# SENSOR.net
KiCad netlist of a schematic drawn in Altium Designer
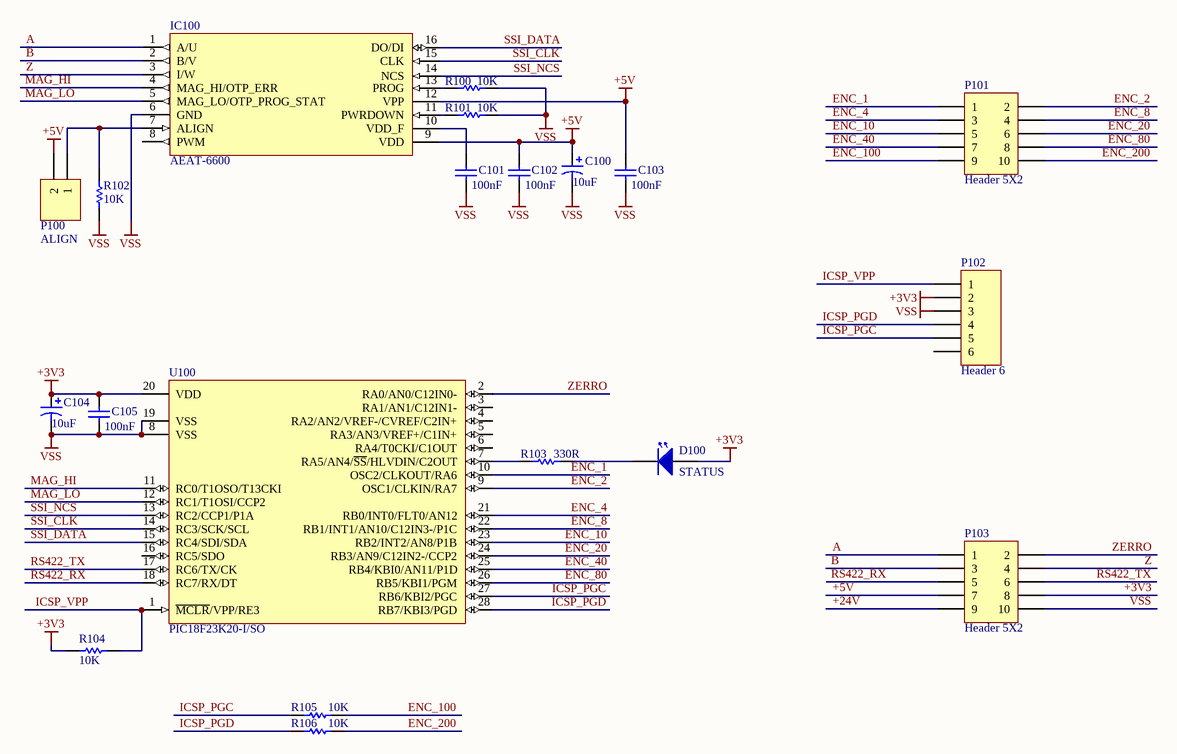
[diagram p0: SENSOR.SchDoc]

(export (version "E")
  (design (tool "Eeschema 10.0.6"))
  (components
    (comp (ref "C100")
      (value "10uF")
      (footprint "C")
      (description "Solid Aluminum Capacitor with Organic Semiconductor Electrolyte: 10uF, 16V, Bulk Pack")
      (fields (field (name "PUBLISHER") "Altium Limited"))
      (libsource (lib "Vishay Electrolytic Radial-Lead Capacitor") (part "94SC106X0016CBP"))
    )
    (comp (ref "C101")
      (value "100nF")
      (footprint "0805")
      (description "Ceramic Chip Capacitor - Standard")
      (fields (field (name "PUBLISHER") "Altium Limited"))
      (libsource (lib "KEMET Chip Capacitor") (part "C0805"))
    )
    (comp (ref "C102")
      (value "100nF")
      (footprint "0805")
      (description "Ceramic Chip Capacitor - Standard")
      (fields (field (name "PUBLISHER") "Altium Limited"))
      (libsource (lib "KEMET Chip Capacitor") (part "C0805"))
    )
    (comp (ref "C103")
      (value "100nF")
      (footprint "0805")
      (description "Ceramic Chip Capacitor - Standard")
      (fields (field (name "PUBLISHER") "Altium Limited"))
      (libsource (lib "KEMET Chip Capacitor") (part "C0805"))
    )
    (comp (ref "C104")
      (value "10uF")
      (footprint "C")
      (description "Solid Aluminum Capacitor with Organic Semiconductor Electrolyte: 10uF, 16V, Bulk Pack")
      (fields (field (name "PUBLISHER") "Altium Limited"))
      (libsource (lib "Vishay Electrolytic Radial-Lead Capacitor") (part "94SC106X0016CBP"))
    )
    (comp (ref "C105")
      (value "100nF")
      (footprint "0805")
      (description "Ceramic Chip Capacitor - Standard")
      (fields (field (name "PUBLISHER") "Altium Limited"))
      (libsource (lib "KEMET Chip Capacitor") (part "C0805"))
    )
    (comp (ref "D100")
      (value "STATUS")
      (footprint "LED 3mm")
      (description "LED dioda 3 mm")
      (libsource (lib "Schlib1") (part "LED 3mm yellow"))
    )
    (comp (ref "IC100")
      (value "AEAT-6600")
      (footprint "TSSOP16")
      (description "Absolute encoder IC")
      (libsource (lib "ABS_ENC") (part "AEAT-6600"))
    )
    (comp (ref "P100")
      (value "ALIGN")
      (footprint "HDR1X2")
      (description "Header, 2-Pin")
      (fields (field (name "PUBLISHER") "Altium Limited"))
      (libsource (lib "Miscellaneous Connectors") (part "Header 2"))
    )
    (comp (ref "P101")
      (value "Header 5X2")
      (footprint "HDR2X5")
      (description "Header, 5-Pin, Dual row")
      (fields (field (name "PUBLISHER") "Altium Limited"))
      (libsource (lib "Miscellaneous Connectors") (part "Header 5X2"))
    )
    (comp (ref "P102")
      (value "Header 6")
      (footprint "HDR1X6")
      (description "Header, 6-Pin")
      (fields (field (name "PUBLISHER") "Altium Limited"))
      (libsource (lib "Miscellaneous Connectors") (part "Header 6"))
    )
    (comp (ref "P103")
      (value "Header 5X2")
      (footprint "HDR2X5")
      (description "Header, 5-Pin, Dual row")
      (fields (field (name "PUBLISHER") "Altium Limited"))
      (libsource (lib "Miscellaneous Connectors") (part "Header 5X2"))
    )
    (comp (ref "R100")
      (value "10K")
      (footprint "ERA-0603")
      (fields (field (name "PUBLISHER") "Altium Limited"))
      (libsource (lib "Panasonic Resistor") (part "ERAV"))
    )
    (comp (ref "R101")
      (value "10K")
      (footprint "ERA-0603")
      (fields (field (name "PUBLISHER") "Altium Limited"))
      (libsource (lib "Panasonic Resistor") (part "ERAV"))
    )
    (comp (ref "R102")
      (value "10K")
      (footprint "ERA-0603")
      (fields (field (name "PUBLISHER") "Altium Limited"))
      (libsource (lib "Panasonic Resistor") (part "ERAV"))
    )
    (comp (ref "R103")
      (value "330R")
      (footprint "ERA-0603")
      (fields (field (name "PUBLISHER") "Altium Limited"))
      (libsource (lib "Panasonic Resistor") (part "ERAV"))
    )
    (comp (ref "R104")
      (value "10K")
      (footprint "ERA-0603")
      (fields (field (name "PUBLISHER") "Altium Limited"))
      (libsource (lib "Panasonic Resistor") (part "ERAV"))
    )
    (comp (ref "R105")
      (value "10K")
      (footprint "ERA-0603")
      (fields (field (name "PUBLISHER") "Altium Limited"))
      (libsource (lib "Panasonic Resistor") (part "ERAV"))
    )
    (comp (ref "R106")
      (value "10K")
      (footprint "ERA-0603")
      (fields (field (name "PUBLISHER") "Altium Limited"))
      (libsource (lib "Panasonic Resistor") (part "ERAV"))
    )
    (comp (ref "U100")
      (value "PIC18F23K20-I/SO")
      (footprint "SOIC-SO28_N")
      (description "Flash Microcontroller with nanoWatt XLP Technology, 28-pin SOIC, Industrial Temperature")
      (fields (field (name "PUBLISHER") "Altium Limited"))
      (libsource (lib "Microchip Microcontroller 8-Bit PIC18") (part "PIC18F23K20-I/SO"))
    )
  )
  (nets
    (net (code "1") (name "+3V3") (class "Default")
      (node (ref "C104") (pin "1") (pinfunction "1_1") (pintype "passive"))
      (node (ref "C105") (pin "2") (pinfunction "2_2") (pintype "passive"))
      (node (ref "D100") (pin "2") (pinfunction "2_2") (pintype "passive"))
      (node (ref "P102") (pin "2") (pinfunction "2_2") (pintype "passive"))
      (node (ref "P103") (pin "8") (pinfunction "8_8") (pintype "passive"))
      (node (ref "R104") (pin "2") (pinfunction "2_2") (pintype "passive"))
      (node (ref "U100") (pin "20") (pinfunction "VDD_20") (pintype "power_in"))
    )
    (net (code "2") (name "+5V") (class "Default")
      (node (ref "C100") (pin "1") (pinfunction "1_1") (pintype "passive"))
      (node (ref "C102") (pin "2") (pinfunction "2_2") (pintype "passive"))
      (node (ref "C103") (pin "2") (pinfunction "2_2") (pintype "passive"))
      (node (ref "IC100") (pin "12") (pinfunction "VPP_12") (pintype "power_in"))
      (node (ref "IC100") (pin "9") (pinfunction "VDD_9") (pintype "power_in"))
      (node (ref "P100") (pin "2") (pinfunction "2_2") (pintype "passive"))
      (node (ref "P103") (pin "7") (pinfunction "7_7") (pintype "passive"))
    )
    (net (code "3") (name "/+24V") (class "Default")
      (node (ref "P103") (pin "9") (pinfunction "9_9") (pintype "passive"))
    )
    (net (code "4") (name "/A") (class "Default")
      (node (ref "IC100") (pin "1") (pinfunction "A/U_1") (pintype "output"))
      (node (ref "P103") (pin "1") (pinfunction "1_1") (pintype "passive"))
    )
    (net (code "5") (name "/B") (class "Default")
      (node (ref "IC100") (pin "2") (pinfunction "B/V_2") (pintype "output"))
      (node (ref "P103") (pin "3") (pinfunction "3_3") (pintype "passive"))
    )
    (net (code "6") (name "/ENC_1") (class "Default")
      (node (ref "P101") (pin "1") (pinfunction "1_1") (pintype "passive"))
      (node (ref "U100") (pin "10") (pinfunction "OSC2/CLKOUT/RA6_10") (pintype "bidirectional"))
    )
    (net (code "7") (name "/ENC_2") (class "Default")
      (node (ref "P101") (pin "2") (pinfunction "2_2") (pintype "passive"))
      (node (ref "U100") (pin "9") (pinfunction "OSC1/CLKIN/RA7_9") (pintype "bidirectional"))
    )
    (net (code "8") (name "/ENC_4") (class "Default")
      (node (ref "P101") (pin "3") (pinfunction "3_3") (pintype "passive"))
      (node (ref "U100") (pin "21") (pinfunction "RB0/INT0/FLT0/AN12_21") (pintype "bidirectional"))
    )
    (net (code "9") (name "/ENC_8") (class "Default")
      (node (ref "P101") (pin "4") (pinfunction "4_4") (pintype "passive"))
      (node (ref "U100") (pin "22") (pinfunction "RB1/INT1/AN10/C12IN3-/P1C_22") (pintype "bidirectional"))
    )
    (net (code "10") (name "/ENC_10") (class "Default")
      (node (ref "P101") (pin "5") (pinfunction "5_5") (pintype "passive"))
      (node (ref "U100") (pin "23") (pinfunction "RB2/INT2/AN8/P1B_23") (pintype "bidirectional"))
    )
    (net (code "11") (name "/ENC_20") (class "Default")
      (node (ref "P101") (pin "6") (pinfunction "6_6") (pintype "passive"))
      (node (ref "U100") (pin "24") (pinfunction "RB3/AN9/C12IN2-/CCP2_24") (pintype "bidirectional"))
    )
    (net (code "12") (name "/ENC_40") (class "Default")
      (node (ref "P101") (pin "7") (pinfunction "7_7") (pintype "passive"))
      (node (ref "U100") (pin "25") (pinfunction "RB4/KBI0/AN11/P1D_25") (pintype "bidirectional"))
    )
    (net (code "13") (name "/ENC_80") (class "Default")
      (node (ref "P101") (pin "8") (pinfunction "8_8") (pintype "passive"))
      (node (ref "U100") (pin "26") (pinfunction "RB5/KBI1/PGM_26") (pintype "bidirectional"))
    )
    (net (code "14") (name "/ENC_100") (class "Default")
      (node (ref "P101") (pin "9") (pinfunction "9_9") (pintype "passive"))
      (node (ref "R105") (pin "1") (pinfunction "1_1") (pintype "passive"))
    )
    (net (code "15") (name "/ENC_200") (class "Default")
      (node (ref "P101") (pin "10") (pinfunction "10_10") (pintype "passive"))
      (node (ref "R106") (pin "1") (pinfunction "1_1") (pintype "passive"))
    )
    (net (code "16") (name "/ICSP_PGC") (class "Default")
      (node (ref "P102") (pin "5") (pinfunction "5_5") (pintype "passive"))
      (node (ref "R105") (pin "2") (pinfunction "2_2") (pintype "passive"))
      (node (ref "U100") (pin "27") (pinfunction "RB6/KBI2/PGC_27") (pintype "bidirectional"))
    )
    (net (code "17") (name "/ICSP_PGD") (class "Default")
      (node (ref "P102") (pin "4") (pinfunction "4_4") (pintype "passive"))
      (node (ref "R106") (pin "2") (pinfunction "2_2") (pintype "passive"))
      (node (ref "U100") (pin "28") (pinfunction "RB7/KBI3/PGD_28") (pintype "bidirectional"))
    )
    (net (code "18") (name "/ICSP_VPP") (class "Default")
      (node (ref "P102") (pin "1") (pinfunction "1_1") (pintype "passive"))
      (node (ref "R104") (pin "1") (pinfunction "1_1") (pintype "passive"))
      (node (ref "U100") (pin "1") (pinfunction "~{MCLR}/VPP/RE3_1") (pintype "input"))
    )
    (net (code "19") (name "/MAG_HI") (class "Default")
      (node (ref "IC100") (pin "4") (pinfunction "MAG_HI/OTP_ERR_4") (pintype "output"))
      (node (ref "U100") (pin "11") (pinfunction "RC0/T1OSO/T13CKI_11") (pintype "bidirectional"))
    )
    (net (code "20") (name "/MAG_LO") (class "Default")
      (node (ref "IC100") (pin "5") (pinfunction "MAG_LO/OTP_PROG_STAT_5") (pintype "output"))
      (node (ref "U100") (pin "12") (pinfunction "RC1/T1OSI/CCP2_12") (pintype "bidirectional"))
    )
    (net (code "21") (name "/RS422_RX") (class "Default")
      (node (ref "P103") (pin "5") (pinfunction "5_5") (pintype "passive"))
      (node (ref "U100") (pin "18") (pinfunction "RC7/RX/DT_18") (pintype "bidirectional"))
    )
    (net (code "22") (name "/RS422_TX") (class "Default")
      (node (ref "P103") (pin "6") (pinfunction "6_6") (pintype "passive"))
      (node (ref "U100") (pin "17") (pinfunction "RC6/TX/CK_17") (pintype "bidirectional"))
    )
    (net (code "23") (name "/SSI_CLK") (class "Default")
      (node (ref "IC100") (pin "15") (pinfunction "CLK_15") (pintype "input"))
      (node (ref "U100") (pin "14") (pinfunction "RC3/SCK/SCL_14") (pintype "bidirectional"))
    )
    (net (code "24") (name "/SSI_DATA") (class "Default")
      (node (ref "IC100") (pin "16") (pinfunction "DO/DI_16") (pintype "bidirectional"))
      (node (ref "U100") (pin "15") (pinfunction "RC4/SDI/SDA_15") (pintype "bidirectional"))
    )
    (net (code "25") (name "/SSI_NCS") (class "Default")
      (node (ref "IC100") (pin "14") (pinfunction "NCS_14") (pintype "input"))
      (node (ref "U100") (pin "13") (pinfunction "RC2/CCP1/P1A_13") (pintype "bidirectional"))
    )
    (net (code "26") (name "/Z") (class "Default")
      (node (ref "IC100") (pin "3") (pinfunction "I/W_3") (pintype "output"))
      (node (ref "P103") (pin "4") (pinfunction "4_4") (pintype "passive"))
    )
    (net (code "27") (name "/ZERRO") (class "Default")
      (node (ref "P103") (pin "2") (pinfunction "2_2") (pintype "passive"))
      (node (ref "U100") (pin "2") (pinfunction "RA0/AN0/C12IN0-_2") (pintype "bidirectional"))
    )
    (net (code "28") (name "Net-(D100-Pad1)") (class "Default")
      (node (ref "D100") (pin "1") (pinfunction "1_1") (pintype "passive"))
      (node (ref "R103") (pin "2") (pinfunction "2_2") (pintype "passive"))
    )
    (net (code "29") (name "Net-(IC100-ALIGN)") (class "Default")
      (node (ref "IC100") (pin "7") (pinfunction "ALIGN_7") (pintype "input"))
      (node (ref "P100") (pin "1") (pinfunction "1_1") (pintype "passive"))
      (node (ref "R102") (pin "2") (pinfunction "2_2") (pintype "passive"))
    )
    (net (code "30") (name "Net-(IC100-PROG)") (class "Default")
      (node (ref "IC100") (pin "13") (pinfunction "PROG_13") (pintype "input"))
      (node (ref "R100") (pin "2") (pinfunction "2_2") (pintype "passive"))
    )
    (net (code "31") (name "Net-(IC100-PWRDOWN)") (class "Default")
      (node (ref "IC100") (pin "11") (pinfunction "PWRDOWN_11") (pintype "input"))
      (node (ref "R101") (pin "2") (pinfunction "2_2") (pintype "passive"))
    )
    (net (code "32") (name "Net-(IC100-VDD_F)") (class "Default")
      (node (ref "C101") (pin "2") (pinfunction "2_2") (pintype "passive"))
      (node (ref "IC100") (pin "10") (pinfunction "VDD_F_10") (pintype "power_in"))
    )
    (net (code "33") (name "Net-(U100-RA5{slash}AN4{slash}~{SS}{slash}HLVDIN{slash}C2OUT)") (class "Default")
      (node (ref "R103") (pin "1") (pinfunction "1_1") (pintype "passive"))
      (node (ref "U100") (pin "7") (pinfunction "RA5/AN4/~{SS}/HLVDIN/C2OUT_7") (pintype "bidirectional"))
    )
    (net (code "34") (name "VSS") (class "Default")
      (node (ref "C100") (pin "2") (pinfunction "2_2") (pintype "passive"))
      (node (ref "C101") (pin "1") (pinfunction "1_1") (pintype "passive"))
      (node (ref "C102") (pin "1") (pinfunction "1_1") (pintype "passive"))
      (node (ref "C103") (pin "1") (pinfunction "1_1") (pintype "passive"))
      (node (ref "C104") (pin "2") (pinfunction "2_2") (pintype "passive"))
      (node (ref "C105") (pin "1") (pinfunction "1_1") (pintype "passive"))
      (node (ref "IC100") (pin "6") (pinfunction "GND_6") (pintype "power_in"))
      (node (ref "P102") (pin "3") (pinfunction "3_3") (pintype "passive"))
      (node (ref "P103") (pin "10") (pinfunction "10_10") (pintype "passive"))
      (node (ref "R100") (pin "1") (pinfunction "1_1") (pintype "passive"))
      (node (ref "R101") (pin "1") (pinfunction "1_1") (pintype "passive"))
      (node (ref "R102") (pin "1") (pinfunction "1_1") (pintype "passive"))
      (node (ref "U100") (pin "19") (pinfunction "VSS_19") (pintype "power_in"))
      (node (ref "U100") (pin "8") (pinfunction "VSS_8") (pintype "power_in"))
    )
    (net (code "35") (name "unconnected-(IC100-PWM-Pad8)") (class "Default")
      (node (ref "IC100") (pin "8") (pinfunction "PWM_8") (pintype "output"))
    )
    (net (code "36") (name "unconnected-(P102-Pad6)") (class "Default")
      (node (ref "P102") (pin "6") (pinfunction "6_6") (pintype "passive"))
    )
    (net (code "37") (name "unconnected-(U100-RA1{slash}AN1{slash}C12IN1--Pad3)") (class "Default")
      (node (ref "U100") (pin "3") (pinfunction "RA1/AN1/C12IN1-_3") (pintype "bidirectional"))
    )
    (net (code "38") (name "unconnected-(U100-RA2{slash}AN2{slash}VREF-{slash}CVREF{slash}C2IN+-Pad4)") (class "Default")
      (node (ref "U100") (pin "4") (pinfunction "RA2/AN2/VREF-/CVREF/C2IN+_4") (pintype "bidirectional"))
    )
    (net (code "39") (name "unconnected-(U100-RA3{slash}AN3{slash}VREF+{slash}C1IN+-Pad5)") (class "Default")
      (node (ref "U100") (pin "5") (pinfunction "RA3/AN3/VREF+/C1IN+_5") (pintype "bidirectional"))
    )
    (net (code "40") (name "unconnected-(U100-RA4{slash}T0CKI{slash}C1OUT-Pad6)") (class "Default")
      (node (ref "U100") (pin "6") (pinfunction "RA4/T0CKI/C1OUT_6") (pintype "bidirectional"))
    )
    (net (code "41") (name "unconnected-(U100-RC5{slash}SDO-Pad16)") (class "Default")
      (node (ref "U100") (pin "16") (pinfunction "RC5/SDO_16") (pintype "bidirectional"))
    )
  )
)
